# Controller.net
KiCad netlist of a schematic drawn in Altium Designer
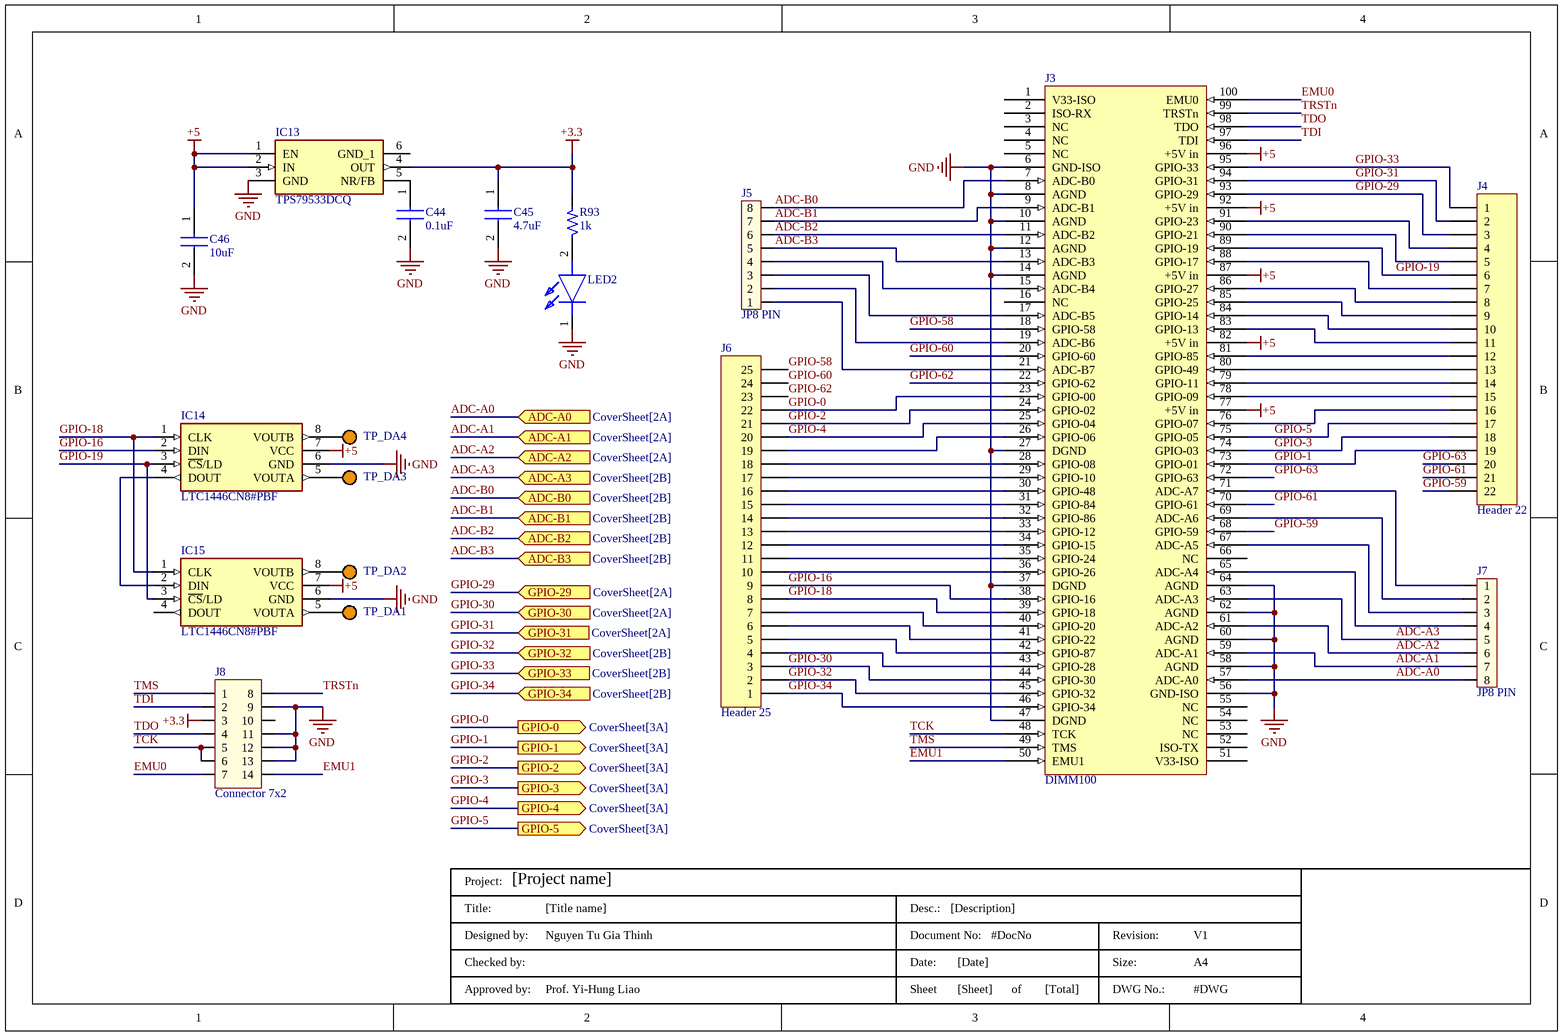
[diagram p0: Controller.SchDoc]

(export (version "E")
  (design (tool "Eeschema 10.0.6"))
  (components
    (comp (ref "C44")
      (value "C0805C104K3RACTU")
      (footprint "SamacSys:C0805")
      (description "Capacitor")
      (fields (field (name "MOUSER PART NUMBER") "80-C0805C104K3R") (field (name "CAPACITANCE") "0.1uF"))
      (libsource (lib "SamacSys") (part "C0805C104K3RACTU"))
    )
    (comp (ref "C45")
      (value "0805B475K250CT")
      (footprint "SamacSys:CAPC2012X145N")
      (description "Capacitor")
      (fields (field (name "MOUSER PART NUMBER") "791-0805B475K250CT") (field (name "CAPACITANCE") "4.7uF"))
      (libsource (lib "SamacSys") (part "0805B475K250CT"))
    )
    (comp (ref "C46")
      (value "C1206C106K3RACTU")
      (footprint "SamacSys:C1206")
      (description "Capacitor")
      (fields (field (name "MOUSER PART NUMBER") "80-C1206C106K3R") (field (name "CAPACITANCE") "10uF"))
      (libsource (lib "SamacSys") (part "C1206C106K3RACTU"))
    )
    (comp (ref "IC13")
      (value "TPS79533DCQ")
      (footprint "SamacSys:SOT127P706X180-6N")
      (description "Integrated Circuit")
      (fields (field (name "MOUSER PART NUMBER") "595-TPS79533DCQ"))
      (libsource (lib "SamacSys") (part "TPS79533DCQ"))
    )
    (comp (ref "IC14")
      (value "LTC1446CN8#PBF")
      (footprint "SamacSys:DIP794W53P254L1016H394Q8N")
      (description "Integrated Circuit")
      (fields (field (name "MOUSER PART NUMBER") "584-LTC1446CN8#PBF"))
      (libsource (lib "SamacSys") (part "LTC1446CN8#PBF"))
    )
    (comp (ref "IC15")
      (value "LTC1446CN8#PBF")
      (footprint "SamacSys:DIP794W53P254L1016H394Q8N")
      (description "Integrated Circuit")
      (fields (field (name "MOUSER PART NUMBER") "584-LTC1446CN8#PBF"))
      (libsource (lib "SamacSys") (part "LTC1446CN8#PBF"))
    )
    (comp (ref "J3")
      (value "DIMM100")
      (footprint "DIMM100")
      (description "DM - Series DIMM Sockets vertical type 100-pin")
      (libsource (lib "ViennaRectifier") (part "DIMM100"))
    )
    (comp (ref "J4")
      (value "Header 22")
      (footprint "HDR1X22")
      (description "Header, 22-Pin")
      (fields (field (name "PUBLISHER") "Altium Limited"))
      (libsource (lib "Cty1") (part "Header 22"))
    )
    (comp (ref "J5") (value "JP8 PIN") (footprint "JP8") (libsource (lib "") (part "JP8_1")))
    (comp (ref "J6")
      (value "Header 25")
      (footprint "HDR1X25")
      (description "Header, 25-Pin")
      (fields (field (name "PUBLISHER") "Altium Limited"))
      (libsource (lib "Cty1") (part "Header 25"))
    )
    (comp (ref "J7") (value "JP8 PIN") (footprint "JP8") (libsource (lib "Cty1") (part "JP8")))
    (comp (ref "J8") (value "Connector 7x2") (footprint "JP7X2") (libsource (lib "Cty1") (part "JP7x2")))
    (comp (ref "LED2")
      (value "150080VS75000")
      (footprint "SamacSys:LEDC2012X80N")
      (description "LED")
      (fields (field (name "MOUSER PART NUMBER") "710-150080VS75000"))
      (libsource (lib "ViennaRectifier") (part "150080VS75000"))
    )
    (comp (ref "R93")
      (value "1k")
      (footprint "SM-1206")
      (description "Resistor 1/4W")
      (libsource (lib "ViennaRectifier") (part "R"))
    )
    (comp (ref "TP_DA1")
      (value "~")
      (footprint "5003")
      (description "Test Point Orrange, Multipurpose, TH")
      (libsource (lib "TestPointKeystone") (part "5003"))
    )
    (comp (ref "TP_DA2")
      (value "~")
      (footprint "5003")
      (description "Test Point Orrange, Multipurpose, TH")
      (libsource (lib "TestPointKeystone") (part "5003"))
    )
    (comp (ref "TP_DA3")
      (value "~")
      (footprint "5003")
      (description "Test Point Orrange, Multipurpose, TH")
      (libsource (lib "TestPointKeystone") (part "5003"))
    )
    (comp (ref "TP_DA4")
      (value "~")
      (footprint "5003")
      (description "Test Point Orrange, Multipurpose, TH")
      (libsource (lib "TestPointKeystone") (part "5003"))
    )
  )
  (nets
    (net (code "1") (name "+3.3") (class "Default")
      (node (ref "C45") (pin "1") (pinfunction "1_1") (pintype "passive"))
      (node (ref "IC13") (pin "4") (pinfunction "OUT_4") (pintype "output"))
      (node (ref "J8") (pin "3") (pinfunction "3_3") (pintype "passive"))
      (node (ref "R93") (pin "2") (pinfunction "2_2") (pintype "passive"))
    )
    (net (code "2") (name "+5") (class "Default")
      (node (ref "C46") (pin "1") (pinfunction "1_1") (pintype "passive"))
      (node (ref "IC13") (pin "1") (pinfunction "EN_1") (pintype "passive"))
      (node (ref "IC13") (pin "2") (pinfunction "IN_2") (pintype "input"))
      (node (ref "IC14") (pin "7") (pinfunction "VCC_7") (pintype "power_in"))
      (node (ref "IC15") (pin "7") (pinfunction "VCC_7") (pintype "power_in"))
      (node (ref "J3") (pin "77") (pinfunction "+5V_in_77") (pintype "power_in"))
      (node (ref "J3") (pin "82") (pinfunction "+5V_in_82") (pintype "power_in"))
      (node (ref "J3") (pin "87") (pinfunction "+5V_in_87") (pintype "power_in"))
      (node (ref "J3") (pin "92") (pinfunction "+5V_in_92") (pintype "power_in"))
      (node (ref "J3") (pin "96") (pinfunction "+5V_in_96") (pintype "power_in"))
    )
    (net (code "3") (name "/ADC-A0") (class "Default")
      (node (ref "J3") (pin "57") (pinfunction "ADC-A0_57") (pintype "input"))
      (node (ref "J7") (pin "8") (pinfunction "8_8") (pintype "passive"))
    )
    (net (code "4") (name "/ADC-A1") (class "Default")
      (node (ref "J3") (pin "59") (pinfunction "ADC-A1_59") (pintype "input"))
      (node (ref "J7") (pin "7") (pinfunction "7_7") (pintype "passive"))
    )
    (net (code "5") (name "/ADC-A2") (class "Default")
      (node (ref "J3") (pin "61") (pinfunction "ADC-A2_61") (pintype "input"))
      (node (ref "J7") (pin "6") (pinfunction "6_6") (pintype "passive"))
    )
    (net (code "6") (name "/ADC-A3") (class "Default")
      (node (ref "J3") (pin "63") (pinfunction "ADC-A3_63") (pintype "input"))
      (node (ref "J7") (pin "5") (pinfunction "5_5") (pintype "passive"))
    )
    (net (code "7") (name "/ADC-B0") (class "Default")
      (node (ref "J3") (pin "7") (pinfunction "ADC-B0_7") (pintype "input"))
      (node (ref "J5") (pin "8") (pinfunction "8_8") (pintype "passive"))
    )
    (net (code "8") (name "/ADC-B1") (class "Default")
      (node (ref "J3") (pin "9") (pinfunction "ADC-B1_9") (pintype "input"))
      (node (ref "J5") (pin "7") (pinfunction "7_7") (pintype "passive"))
    )
    (net (code "9") (name "/ADC-B2") (class "Default")
      (node (ref "J3") (pin "11") (pinfunction "ADC-B2_11") (pintype "input"))
      (node (ref "J5") (pin "6") (pinfunction "6_6") (pintype "passive"))
    )
    (net (code "10") (name "/ADC-B3") (class "Default")
      (node (ref "J3") (pin "13") (pinfunction "ADC-B3_13") (pintype "input"))
      (node (ref "J5") (pin "5") (pinfunction "5_5") (pintype "passive"))
    )
    (net (code "11") (name "/EMU0") (class "Default")
      (node (ref "J3") (pin "100") (pinfunction "EMU0_100") (pintype "input"))
      (node (ref "J8") (pin "7") (pinfunction "7_7") (pintype "passive"))
    )
    (net (code "12") (name "/EMU1") (class "Default")
      (node (ref "J3") (pin "50") (pinfunction "EMU1_50") (pintype "input"))
      (node (ref "J8") (pin "14") (pinfunction "14_14") (pintype "passive"))
    )
    (net (code "13") (name "/GPIO-0") (class "Default")
      (node (ref "J3") (pin "23") (pinfunction "GPIO-00_23") (pintype "input"))
      (node (ref "J6") (pin "22") (pinfunction "22_22") (pintype "passive"))
    )
    (net (code "14") (name "/GPIO-1") (class "Default")
      (node (ref "J3") (pin "73") (pinfunction "GPIO-01_73") (pintype "input"))
      (node (ref "J4") (pin "19") (pinfunction "19_19") (pintype "passive"))
    )
    (net (code "15") (name "/GPIO-2") (class "Default")
      (node (ref "J3") (pin "24") (pinfunction "GPIO-02_24") (pintype "input"))
      (node (ref "J6") (pin "21") (pinfunction "21_21") (pintype "passive"))
    )
    (net (code "16") (name "/GPIO-3") (class "Default")
      (node (ref "J3") (pin "74") (pinfunction "GPIO-03_74") (pintype "input"))
      (node (ref "J4") (pin "18") (pinfunction "18_18") (pintype "passive"))
    )
    (net (code "17") (name "/GPIO-4") (class "Default")
      (node (ref "J3") (pin "25") (pinfunction "GPIO-04_25") (pintype "input"))
      (node (ref "J6") (pin "20") (pinfunction "20_20") (pintype "passive"))
    )
    (net (code "18") (name "/GPIO-5") (class "Default")
      (node (ref "J3") (pin "75") (pinfunction "GPIO-05_75") (pintype "input"))
      (node (ref "J4") (pin "17") (pinfunction "17_17") (pintype "passive"))
    )
    (net (code "19") (name "/GPIO-16") (class "Default")
      (node (ref "IC14") (pin "2") (pinfunction "DIN_2") (pintype "input"))
      (node (ref "J3") (pin "38") (pinfunction "GPIO-16_38") (pintype "input"))
      (node (ref "J6") (pin "9") (pinfunction "9_9") (pintype "passive"))
    )
    (net (code "20") (name "/GPIO-18") (class "Default")
      (node (ref "IC14") (pin "1") (pinfunction "CLK_1") (pintype "input"))
      (node (ref "IC15") (pin "1") (pinfunction "CLK_1") (pintype "input"))
      (node (ref "J3") (pin "39") (pinfunction "GPIO-18_39") (pintype "input"))
      (node (ref "J6") (pin "8") (pinfunction "8_8") (pintype "passive"))
    )
    (net (code "21") (name "/GPIO-19") (class "Default")
      (node (ref "IC14") (pin "3") (pinfunction "~{CS}/LD_3") (pintype "input"))
      (node (ref "IC15") (pin "3") (pinfunction "~{CS}/LD_3") (pintype "input"))
      (node (ref "J3") (pin "89") (pinfunction "GPIO-19_89") (pintype "input"))
      (node (ref "J4") (pin "6") (pinfunction "6_6") (pintype "passive"))
    )
    (net (code "22") (name "/GPIO-29") (class "Default")
      (node (ref "J3") (pin "93") (pinfunction "GPIO-29_93") (pintype "input"))
      (node (ref "J4") (pin "3") (pinfunction "3_3") (pintype "passive"))
    )
    (net (code "23") (name "/GPIO-30") (class "Default")
      (node (ref "J3") (pin "44") (pinfunction "GPIO-30_44") (pintype "input"))
      (node (ref "J6") (pin "3") (pinfunction "3_3") (pintype "passive"))
    )
    (net (code "24") (name "/GPIO-31") (class "Default")
      (node (ref "J3") (pin "94") (pinfunction "GPIO-31_94") (pintype "input"))
      (node (ref "J4") (pin "2") (pinfunction "2_2") (pintype "passive"))
    )
    (net (code "25") (name "/GPIO-32") (class "Default")
      (node (ref "J3") (pin "45") (pinfunction "GPIO-32_45") (pintype "input"))
      (node (ref "J6") (pin "2") (pinfunction "2_2") (pintype "passive"))
    )
    (net (code "26") (name "/GPIO-33") (class "Default")
      (node (ref "J3") (pin "95") (pinfunction "GPIO-33_95") (pintype "input"))
      (node (ref "J4") (pin "1") (pinfunction "1_1") (pintype "passive"))
    )
    (net (code "27") (name "/GPIO-34") (class "Default")
      (node (ref "J3") (pin "46") (pinfunction "GPIO-34_46") (pintype "input"))
      (node (ref "J6") (pin "1") (pinfunction "1_1") (pintype "passive"))
    )
    (net (code "28") (name "/GPIO-58") (class "Default")
      (node (ref "J3") (pin "18") (pinfunction "GPIO-58_18") (pintype "input"))
      (node (ref "J6") (pin "25") (pinfunction "25_25") (pintype "passive"))
    )
    (net (code "29") (name "/GPIO-59") (class "Default")
      (node (ref "J3") (pin "68") (pinfunction "GPIO-59_68") (pintype "input"))
      (node (ref "J4") (pin "22") (pinfunction "22_22") (pintype "passive"))
    )
    (net (code "30") (name "/GPIO-60") (class "Default")
      (node (ref "J3") (pin "20") (pinfunction "GPIO-60_20") (pintype "input"))
      (node (ref "J6") (pin "24") (pinfunction "24_24") (pintype "passive"))
    )
    (net (code "31") (name "/GPIO-61") (class "Default")
      (node (ref "J3") (pin "70") (pinfunction "GPIO-61_70") (pintype "input"))
      (node (ref "J4") (pin "21") (pinfunction "21_21") (pintype "passive"))
    )
    (net (code "32") (name "/GPIO-62") (class "Default")
      (node (ref "J3") (pin "22") (pinfunction "GPIO-62_22") (pintype "input"))
      (node (ref "J6") (pin "23") (pinfunction "23_23") (pintype "passive"))
    )
    (net (code "33") (name "/GPIO-63") (class "Default")
      (node (ref "J3") (pin "72") (pinfunction "GPIO-63_72") (pintype "input"))
      (node (ref "J4") (pin "20") (pinfunction "20_20") (pintype "passive"))
    )
    (net (code "34") (name "/TCK") (class "Default")
      (node (ref "J3") (pin "48") (pinfunction "TCK_48") (pintype "input"))
      (node (ref "J8") (pin "5") (pinfunction "5_5") (pintype "passive"))
      (node (ref "J8") (pin "6") (pinfunction "6_6") (pintype "passive"))
    )
    (net (code "35") (name "/TDI") (class "Default")
      (node (ref "J3") (pin "97") (pinfunction "TDI_97") (pintype "input"))
      (node (ref "J8") (pin "2") (pinfunction "2_2") (pintype "passive"))
    )
    (net (code "36") (name "/TDO") (class "Default")
      (node (ref "J3") (pin "98") (pinfunction "TDO_98") (pintype "input"))
      (node (ref "J8") (pin "4") (pinfunction "4_4") (pintype "passive"))
    )
    (net (code "37") (name "/TMS") (class "Default")
      (node (ref "J3") (pin "49") (pinfunction "TMS_49") (pintype "input"))
      (node (ref "J8") (pin "1") (pinfunction "1_1") (pintype "passive"))
    )
    (net (code "38") (name "/TRSTn") (class "Default")
      (node (ref "J3") (pin "99") (pinfunction "TRSTn_99") (pintype "input"))
      (node (ref "J8") (pin "8") (pinfunction "8_8") (pintype "passive"))
    )
    (net (code "39") (name "GND") (class "Default")
      (node (ref "C44") (pin "2") (pinfunction "2_2") (pintype "passive"))
      (node (ref "C45") (pin "2") (pinfunction "2_2") (pintype "passive"))
      (node (ref "C46") (pin "2") (pinfunction "2_2") (pintype "passive"))
      (node (ref "IC13") (pin "3") (pinfunction "GND_3") (pintype "power_in"))
      (node (ref "IC14") (pin "6") (pinfunction "GND_6") (pintype "power_in"))
      (node (ref "IC15") (pin "6") (pinfunction "GND_6") (pintype "power_in"))
      (node (ref "J3") (pin "10") (pinfunction "AGND_10") (pintype "power_in"))
      (node (ref "J3") (pin "12") (pinfunction "AGND_12") (pintype "power_in"))
      (node (ref "J3") (pin "14") (pinfunction "AGND_14") (pintype "power_in"))
      (node (ref "J3") (pin "27") (pinfunction "DGND_27") (pintype "power_in"))
      (node (ref "J3") (pin "37") (pinfunction "DGND_37") (pintype "power_in"))
      (node (ref "J3") (pin "47") (pinfunction "DGND_47") (pintype "power_in"))
      (node (ref "J3") (pin "56") (pinfunction "GND-ISO_56") (pintype "power_in"))
      (node (ref "J3") (pin "58") (pinfunction "AGND_58") (pintype "power_in"))
      (node (ref "J3") (pin "6") (pinfunction "GND-ISO_6") (pintype "power_in"))
      (node (ref "J3") (pin "60") (pinfunction "AGND_60") (pintype "power_in"))
      (node (ref "J3") (pin "62") (pinfunction "AGND_62") (pintype "power_in"))
      (node (ref "J3") (pin "64") (pinfunction "AGND_64") (pintype "power_in"))
      (node (ref "J3") (pin "8") (pinfunction "AGND_8") (pintype "power_in"))
      (node (ref "J8") (pin "11") (pinfunction "11_11") (pintype "passive"))
      (node (ref "J8") (pin "12") (pinfunction "12_12") (pintype "passive"))
      (node (ref "J8") (pin "13") (pinfunction "13_13") (pintype "passive"))
      (node (ref "J8") (pin "9") (pinfunction "9_9") (pintype "passive"))
      (node (ref "LED2") (pin "1") (pinfunction "K_1") (pintype "passive"))
    )
    (net (code "40") (name "Net-(IC13-NR{slash}FB)") (class "Default")
      (node (ref "C44") (pin "1") (pinfunction "1_1") (pintype "passive"))
      (node (ref "IC13") (pin "5") (pinfunction "NR/FB_5") (pintype "passive"))
    )
    (net (code "41") (name "Net-(IC14-DOUT)") (class "Default")
      (node (ref "IC14") (pin "4") (pinfunction "DOUT_4") (pintype "output"))
      (node (ref "IC15") (pin "2") (pinfunction "DIN_2") (pintype "input"))
    )
    (net (code "42") (name "Net-(IC14-VOUTA)") (class "Default")
      (node (ref "IC14") (pin "5") (pinfunction "VOUTA_5") (pintype "output"))
      (node (ref "TP_DA3") (pin "1") (pinfunction "1_1") (pintype "passive"))
    )
    (net (code "43") (name "Net-(IC14-VOUTB)") (class "Default")
      (node (ref "IC14") (pin "8") (pinfunction "VOUTB_8") (pintype "output"))
      (node (ref "TP_DA4") (pin "1") (pinfunction "1_1") (pintype "passive"))
    )
    (net (code "44") (name "Net-(IC15-VOUTA)") (class "Default")
      (node (ref "IC15") (pin "5") (pinfunction "VOUTA_5") (pintype "output"))
      (node (ref "TP_DA1") (pin "1") (pinfunction "1_1") (pintype "passive"))
    )
    (net (code "45") (name "Net-(IC15-VOUTB)") (class "Default")
      (node (ref "IC15") (pin "8") (pinfunction "VOUTB_8") (pintype "output"))
      (node (ref "TP_DA2") (pin "1") (pinfunction "1_1") (pintype "passive"))
    )
    (net (code "46") (name "Net-(J3-ADC-A4)") (class "Default")
      (node (ref "J3") (pin "65") (pinfunction "ADC-A4_65") (pintype "input"))
      (node (ref "J7") (pin "4") (pinfunction "4_4") (pintype "passive"))
    )
    (net (code "47") (name "Net-(J3-ADC-A5)") (class "Default")
      (node (ref "J3") (pin "67") (pinfunction "ADC-A5_67") (pintype "input"))
      (node (ref "J7") (pin "3") (pinfunction "3_3") (pintype "passive"))
    )
    (net (code "48") (name "Net-(J3-ADC-A6)") (class "Default")
      (node (ref "J3") (pin "69") (pinfunction "ADC-A6_69") (pintype "input"))
      (node (ref "J7") (pin "2") (pinfunction "2_2") (pintype "passive"))
    )
    (net (code "49") (name "Net-(J3-ADC-A7)") (class "Default")
      (node (ref "J3") (pin "71") (pinfunction "ADC-A7_71") (pintype "input"))
      (node (ref "J7") (pin "1") (pinfunction "1_1") (pintype "passive"))
    )
    (net (code "50") (name "Net-(J3-ADC-B4)") (class "Default")
      (node (ref "J3") (pin "15") (pinfunction "ADC-B4_15") (pintype "input"))
      (node (ref "J5") (pin "4") (pinfunction "4_4") (pintype "passive"))
    )
    (net (code "51") (name "Net-(J3-ADC-B5)") (class "Default")
      (node (ref "J3") (pin "17") (pinfunction "ADC-B5_17") (pintype "input"))
      (node (ref "J5") (pin "3") (pinfunction "3_3") (pintype "passive"))
    )
    (net (code "52") (name "Net-(J3-ADC-B6)") (class "Default")
      (node (ref "J3") (pin "19") (pinfunction "ADC-B6_19") (pintype "input"))
      (node (ref "J5") (pin "2") (pinfunction "2_2") (pintype "passive"))
    )
    (net (code "53") (name "Net-(J3-ADC-B7)") (class "Default")
      (node (ref "J3") (pin "21") (pinfunction "ADC-B7_21") (pintype "input"))
      (node (ref "J5") (pin "1") (pinfunction "1_1") (pintype "passive"))
    )
    (net (code "54") (name "Net-(J3-GPIO-06)") (class "Default")
      (node (ref "J3") (pin "26") (pinfunction "GPIO-06_26") (pintype "input"))
      (node (ref "J6") (pin "19") (pinfunction "19_19") (pintype "passive"))
    )
    (net (code "55") (name "Net-(J3-GPIO-07)") (class "Default")
      (node (ref "J3") (pin "76") (pinfunction "GPIO-07_76") (pintype "input"))
      (node (ref "J4") (pin "16") (pinfunction "16_16") (pintype "passive"))
    )
    (net (code "56") (name "Net-(J3-GPIO-08)") (class "Default")
      (node (ref "J3") (pin "28") (pinfunction "GPIO-08_28") (pintype "input"))
      (node (ref "J6") (pin "18") (pinfunction "18_18") (pintype "passive"))
    )
    (net (code "57") (name "Net-(J3-GPIO-09)") (class "Default")
      (node (ref "J3") (pin "78") (pinfunction "GPIO-09_78") (pintype "input"))
      (node (ref "J4") (pin "15") (pinfunction "15_15") (pintype "passive"))
    )
    (net (code "58") (name "Net-(J3-GPIO-10)") (class "Default")
      (node (ref "J3") (pin "29") (pinfunction "GPIO-10_29") (pintype "input"))
      (node (ref "J6") (pin "17") (pinfunction "17_17") (pintype "passive"))
    )
    (net (code "59") (name "Net-(J3-GPIO-11)") (class "Default")
      (node (ref "J3") (pin "79") (pinfunction "GPIO-11_79") (pintype "input"))
      (node (ref "J4") (pin "14") (pinfunction "14_14") (pintype "passive"))
    )
    (net (code "60") (name "Net-(J3-GPIO-12)") (class "Default")
      (node (ref "J3") (pin "33") (pinfunction "GPIO-12_33") (pintype "input"))
      (node (ref "J6") (pin "13") (pinfunction "13_13") (pintype "passive"))
    )
    (net (code "61") (name "Net-(J3-GPIO-13)") (class "Default")
      (node (ref "J3") (pin "83") (pinfunction "GPIO-13_83") (pintype "input"))
      (node (ref "J4") (pin "11") (pinfunction "11_11") (pintype "passive"))
    )
    (net (code "62") (name "Net-(J3-GPIO-14)") (class "Default")
      (node (ref "J3") (pin "84") (pinfunction "GPIO-14_84") (pintype "input"))
      (node (ref "J4") (pin "10") (pinfunction "10_10") (pintype "passive"))
    )
    (net (code "63") (name "Net-(J3-GPIO-15)") (class "Default")
      (node (ref "J3") (pin "34") (pinfunction "GPIO-15_34") (pintype "input"))
      (node (ref "J6") (pin "12") (pinfunction "12_12") (pintype "passive"))
    )
    (net (code "64") (name "Net-(J3-GPIO-17)") (class "Default")
      (node (ref "J3") (pin "88") (pinfunction "GPIO-17_88") (pintype "input"))
      (node (ref "J4") (pin "7") (pinfunction "7_7") (pintype "passive"))
    )
    (net (code "65") (name "Net-(J3-GPIO-20)") (class "Default")
      (node (ref "J3") (pin "40") (pinfunction "GPIO-20_40") (pintype "input"))
      (node (ref "J6") (pin "7") (pinfunction "7_7") (pintype "passive"))
    )
    (net (code "66") (name "Net-(J3-GPIO-21)") (class "Default")
      (node (ref "J3") (pin "90") (pinfunction "GPIO-21_90") (pintype "input"))
      (node (ref "J4") (pin "5") (pinfunction "5_5") (pintype "passive"))
    )
    (net (code "67") (name "Net-(J3-GPIO-22)") (class "Default")
      (node (ref "J3") (pin "41") (pinfunction "GPIO-22_41") (pintype "input"))
      (node (ref "J6") (pin "6") (pinfunction "6_6") (pintype "passive"))
    )
    (net (code "68") (name "Net-(J3-GPIO-23)") (class "Default")
      (node (ref "J3") (pin "91") (pinfunction "GPIO-23_91") (pintype "input"))
      (node (ref "J4") (pin "4") (pinfunction "4_4") (pintype "passive"))
    )
    (net (code "69") (name "Net-(J3-GPIO-24)") (class "Default")
      (node (ref "J3") (pin "35") (pinfunction "GPIO-24_35") (pintype "input"))
      (node (ref "J6") (pin "11") (pinfunction "11_11") (pintype "passive"))
    )
    (net (code "70") (name "Net-(J3-GPIO-25)") (class "Default")
      (node (ref "J3") (pin "85") (pinfunction "GPIO-25_85") (pintype "input"))
      (node (ref "J4") (pin "9") (pinfunction "9_9") (pintype "passive"))
    )
    (net (code "71") (name "Net-(J3-GPIO-26)") (class "Default")
      (node (ref "J3") (pin "36") (pinfunction "GPIO-26_36") (pintype "input"))
      (node (ref "J6") (pin "10") (pinfunction "10_10") (pintype "passive"))
    )
    (net (code "72") (name "Net-(J3-GPIO-27)") (class "Default")
      (node (ref "J3") (pin "86") (pinfunction "GPIO-27_86") (pintype "input"))
      (node (ref "J4") (pin "8") (pinfunction "8_8") (pintype "passive"))
    )
    (net (code "73") (name "Net-(J3-GPIO-28)") (class "Default")
      (node (ref "J3") (pin "43") (pinfunction "GPIO-28_43") (pintype "input"))
      (node (ref "J6") (pin "4") (pinfunction "4_4") (pintype "passive"))
    )
    (net (code "74") (name "Net-(J3-GPIO-48)") (class "Default")
      (node (ref "J3") (pin "30") (pinfunction "GPIO-48_30") (pintype "input"))
      (node (ref "J6") (pin "16") (pinfunction "16_16") (pintype "passive"))
    )
    (net (code "75") (name "Net-(J3-GPIO-49)") (class "Default")
      (node (ref "J3") (pin "80") (pinfunction "GPIO-49_80") (pintype "input"))
      (node (ref "J4") (pin "13") (pinfunction "13_13") (pintype "passive"))
    )
    (net (code "76") (name "Net-(J3-GPIO-84)") (class "Default")
      (node (ref "J3") (pin "31") (pinfunction "GPIO-84_31") (pintype "input"))
      (node (ref "J6") (pin "15") (pinfunction "15_15") (pintype "passive"))
    )
    (net (code "77") (name "Net-(J3-GPIO-85)") (class "Default")
      (node (ref "J3") (pin "81") (pinfunction "GPIO-85_81") (pintype "input"))
      (node (ref "J4") (pin "12") (pinfunction "12_12") (pintype "passive"))
    )
    (net (code "78") (name "Net-(J3-GPIO-86)") (class "Default")
      (node (ref "J3") (pin "32") (pinfunction "GPIO-86_32") (pintype "input"))
      (node (ref "J6") (pin "14") (pinfunction "14_14") (pintype "passive"))
    )
    (net (code "79") (name "Net-(J3-GPIO-87)") (class "Default")
      (node (ref "J3") (pin "42") (pinfunction "GPIO-87_42") (pintype "input"))
      (node (ref "J6") (pin "5") (pinfunction "5_5") (pintype "passive"))
    )
    (net (code "80") (name "Net-(LED2-A)") (class "Default")
      (node (ref "LED2") (pin "2") (pinfunction "A_2") (pintype "passive"))
      (node (ref "R93") (pin "1") (pinfunction "1_1") (pintype "passive"))
    )
    (net (code "81") (name "unconnected-(IC13-GND_1-Pad6)") (class "Default")
      (node (ref "IC13") (pin "6") (pinfunction "GND_1_6") (pintype "power_in"))
    )
    (net (code "82") (name "unconnected-(IC15-DOUT-Pad4)") (class "Default")
      (node (ref "IC15") (pin "4") (pinfunction "DOUT_4") (pintype "output"))
    )
    (net (code "83") (name "unconnected-(J3-ISO-RX-Pad2)") (class "Default")
      (node (ref "J3") (pin "2") (pinfunction "ISO-RX_2") (pintype "passive"))
    )
    (net (code "84") (name "unconnected-(J3-ISO-TX-Pad52)") (class "Default")
      (node (ref "J3") (pin "52") (pinfunction "ISO-TX_52") (pintype "passive"))
    )
    (net (code "85") (name "unconnected-(J3-NC-Pad3)") (class "Default")
      (node (ref "J3") (pin "3") (pinfunction "NC_3") (pintype "open_collector"))
    )
    (net (code "86") (name "unconnected-(J3-NC-Pad4)") (class "Default")
      (node (ref "J3") (pin "4") (pinfunction "NC_4") (pintype "open_collector"))
    )
    (net (code "87") (name "unconnected-(J3-NC-Pad5)") (class "Default")
      (node (ref "J3") (pin "5") (pinfunction "NC_5") (pintype "open_collector"))
    )
    (net (code "88") (name "unconnected-(J3-NC-Pad16)") (class "Default")
      (node (ref "J3") (pin "16") (pinfunction "NC_16") (pintype "open_emitter"))
    )
    (net (code "89") (name "unconnected-(J3-NC-Pad53)") (class "Default")
      (node (ref "J3") (pin "53") (pinfunction "NC_53") (pintype "open_emitter"))
    )
    (net (code "90") (name "unconnected-(J3-NC-Pad54)") (class "Default")
      (node (ref "J3") (pin "54") (pinfunction "NC_54") (pintype "open_emitter"))
    )
    (net (code "91") (name "unconnected-(J3-NC-Pad55)") (class "Default")
      (node (ref "J3") (pin "55") (pinfunction "NC_55") (pintype "open_emitter"))
    )
    (net (code "92") (name "unconnected-(J3-NC-Pad66)") (class "Default")
      (node (ref "J3") (pin "66") (pinfunction "NC_66") (pintype "open_emitter"))
    )
    (net (code "93") (name "unconnected-(J3-V33-ISO-Pad1)") (class "Default")
      (node (ref "J3") (pin "1") (pinfunction "V33-ISO_1") (pintype "power_in"))
    )
    (net (code "94") (name "unconnected-(J3-V33-ISO-Pad51)") (class "Default")
      (node (ref "J3") (pin "51") (pinfunction "V33-ISO_51") (pintype "power_in"))
    )
    (net (code "95") (name "unconnected-(J8-Pad10)") (class "Default")
      (node (ref "J8") (pin "10") (pinfunction "10_10") (pintype "passive"))
    )
  )
)
